# power.net
KiCad netlist of a schematic drawn in Altium Designer
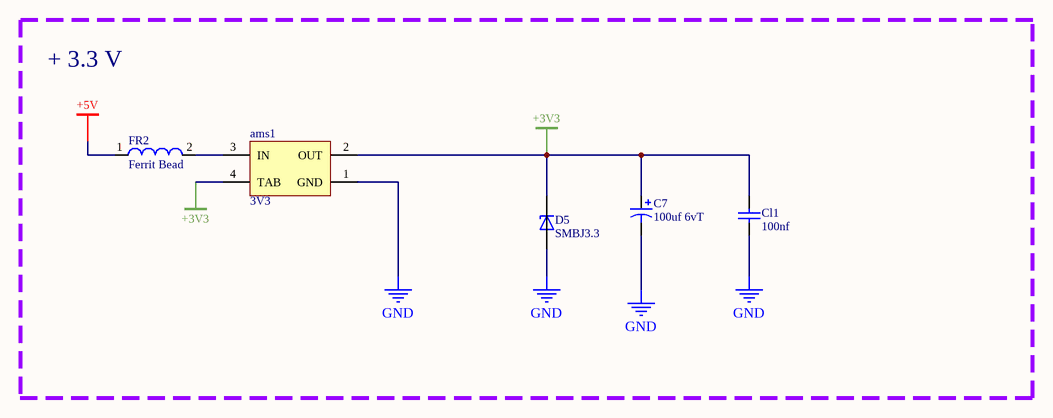
[diagram p0: power.SchDoc]

(export (version "E")
  (design (tool "Eeschema 10.0.6"))
  (components
    (comp (ref "ams1")
      (value "3V3")
      (footprint "SOT223")
      (description "x.x Volt, 800mA Low-Dropout Linear Regulator, 4-pin SOT-223")
      (fields (field (name "DESIGNER") "Ali Hafizi"))
      (libsource (lib "Realy_Box_16_v5") (part "AMS1117-x.x"))
    )
    (comp (ref "C7")
      (value "100uf 6vT")
      (footprint "B")
      (description "Cap/Tantalum/SMD/B")
      (fields (field (name "PUBLISHER") "Altium Limited"))
      (libsource (lib "TOUCH KEY V0") (part "T494B"))
    )
    (comp (ref "Cl1")
      (value "100nf")
      (footprint "RES 0603 (1608X06L)")
      (description "CAP 0805")
      (fields (field (name "DESIGNER") "Abbas Basereh"))
      (libsource (lib "Realy_Box_16_v5") (part "CAP SMD 0805"))
    )
    (comp (ref "D5")
      (value "SMBJ3.3")
      (footprint "DIOM4336X265N")
      (fields (field (name "MF") "{'manufacturer': u'Taiwan Semiconductor'}") (field (name "MP") "SMBJ33"))
      (libsource (lib "SnapEDA_Library") (part "SMBJ33"))
    )
    (comp (ref "FR2")
      (value "Ferrit Bead")
      (footprint "RES 0805 (2012X06L)")
      (libsource (lib "Realy_Box_16_v5") (part "Ferrit Bead"))
    )
  )
  (nets
    (net (code "1") (name "+3V3") (class "Default")
      (node (ref "C7") (pin "1") (pinfunction "1_1") (pintype "passive"))
      (node (ref "Cl1") (pin "2") (pinfunction "2_2") (pintype "passive"))
      (node (ref "D5") (pin "C") (pinfunction "C_C") (pintype "passive"))
      (node (ref "ams1") (pin "2") (pinfunction "OUT_2") (pintype "power_in"))
      (node (ref "ams1") (pin "4") (pinfunction "TAB_4") (pintype "power_in"))
    )
    (net (code "2") (name "+5V") (class "Default")
      (node (ref "FR2") (pin "1") (pinfunction "1_1") (pintype "passive"))
    )
    (net (code "3") (name "GND") (class "Default")
      (node (ref "C7") (pin "2") (pinfunction "2_2") (pintype "passive"))
      (node (ref "Cl1") (pin "1") (pinfunction "1_1") (pintype "passive"))
      (node (ref "D5") (pin "A") (pinfunction "A_A") (pintype "passive"))
      (node (ref "ams1") (pin "1") (pinfunction "GND_1") (pintype "power_in"))
    )
    (net (code "4") (name "Net-(ams1-IN)") (class "Default")
      (node (ref "FR2") (pin "2") (pinfunction "2_2") (pintype "passive"))
      (node (ref "ams1") (pin "3") (pinfunction "IN_3") (pintype "power_in"))
    )
  )
)
